# TemperatureReader.net
KiCad netlist of a schematic drawn in EAGLE
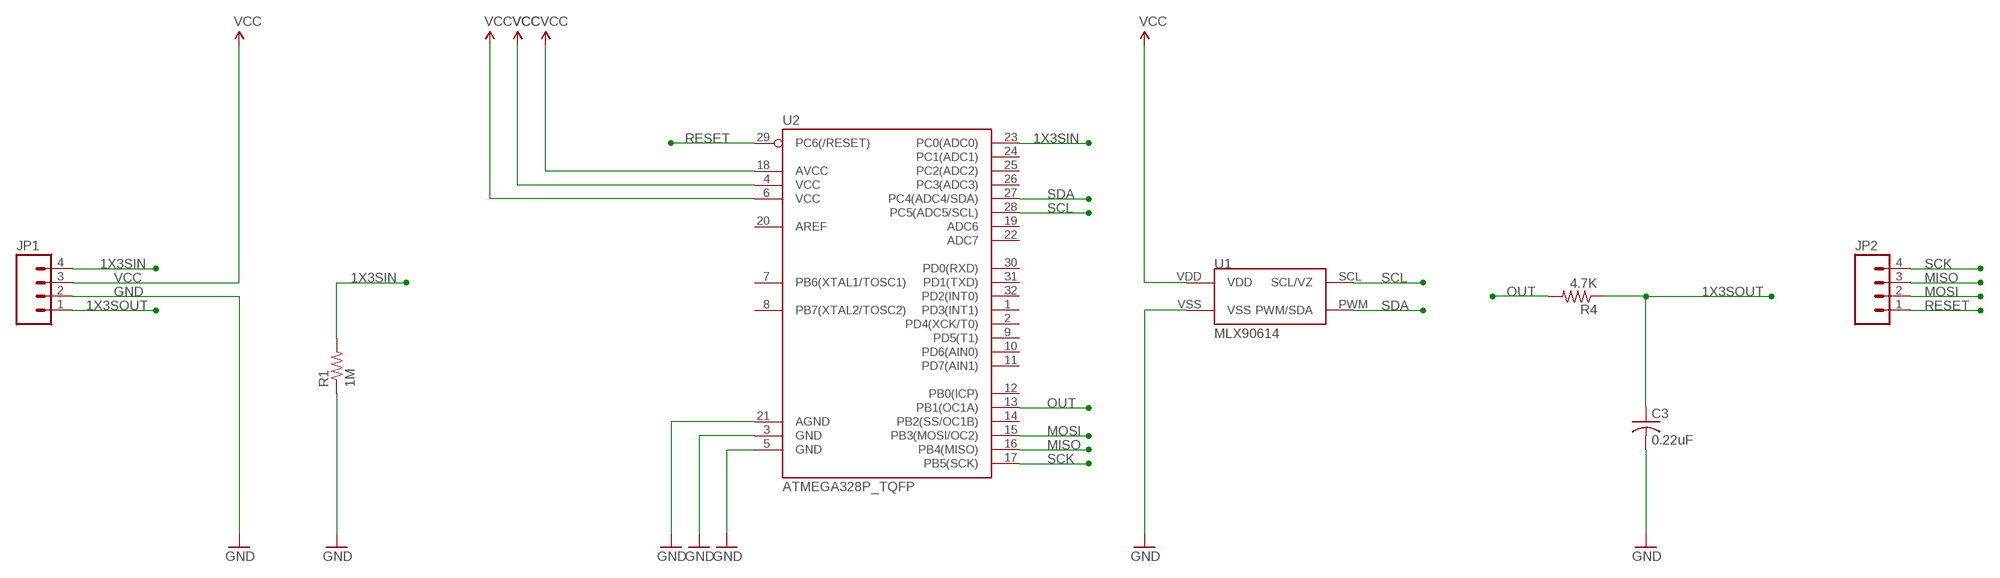
[diagram p0: schematic, sheet 1]

(export (version "E")
  (design (tool "Eeschema 10.0.6"))
  (components
    (comp (ref "C3")
      (value "0.22uF")
      (footprint "eagle-import:C0603")
      (libsource (lib "eagle-import") (part "C-USC0603"))
    )
    (comp (ref "JP1")
      (value "M04PTH")
      (footprint "eagle-import:1X04")
      (libsource (lib "eagle-import") (part "M04PTH"))
    )
    (comp (ref "JP2")
      (value "M04PTH")
      (footprint "eagle-import:1X04")
      (libsource (lib "eagle-import") (part "M04PTH"))
    )
    (comp (ref "R1")
      (value "1M")
      (footprint "eagle-import:R0603")
      (libsource (lib "eagle-import") (part "R-US_R0603"))
    )
    (comp (ref "R4")
      (value "4.7K")
      (footprint "eagle-import:R0603")
      (libsource (lib "eagle-import") (part "R-US_R0603"))
    )
    (comp (ref "U1")
      (value "MLX90614")
      (footprint "eagle-import:TO-39")
      (libsource (lib "eagle-import") (part "MLX90614"))
    )
    (comp (ref "U2")
      (value "ATMEGA328P_TQFP")
      (footprint "eagle-import:TQFP32-08")
      (libsource (lib "eagle-import") (part "ATMEGA328P_TQFP"))
    )
  )
  (nets
    (net (code "1") (name "/1X3SIN") (class "Default")
      (node (ref "JP1") (pin "4") (pinfunction "4_4") (pintype "passive"))
      (node (ref "R1") (pin "2") (pinfunction "2_2") (pintype "passive"))
      (node (ref "U2") (pin "23") (pinfunction "PC0(ADC0)_23") (pintype "bidirectional"))
    )
    (net (code "2") (name "/1X3SOUT") (class "Default")
      (node (ref "C3") (pin "1") (pinfunction "1_1") (pintype "passive"))
      (node (ref "JP1") (pin "1") (pinfunction "1_1") (pintype "passive"))
      (node (ref "R4") (pin "1") (pinfunction "1_1") (pintype "passive"))
    )
    (net (code "3") (name "/MISO") (class "Default")
      (node (ref "JP2") (pin "3") (pinfunction "3_3") (pintype "passive"))
      (node (ref "U2") (pin "16") (pinfunction "PB4(MISO)_16") (pintype "bidirectional"))
    )
    (net (code "4") (name "/MOSI") (class "Default")
      (node (ref "JP2") (pin "2") (pinfunction "2_2") (pintype "passive"))
      (node (ref "U2") (pin "15") (pinfunction "PB3(MOSI/OC2)_15") (pintype "bidirectional"))
    )
    (net (code "5") (name "/OUT") (class "Default")
      (node (ref "R4") (pin "2") (pinfunction "2_2") (pintype "passive"))
      (node (ref "U2") (pin "13") (pinfunction "PB1(OC1A)_13") (pintype "bidirectional"))
    )
    (net (code "6") (name "/RESET") (class "Default")
      (node (ref "JP2") (pin "1") (pinfunction "1_1") (pintype "passive"))
      (node (ref "U2") (pin "29") (pinfunction "PC6(/RESET)_29") (pintype "bidirectional"))
    )
    (net (code "7") (name "/SCK") (class "Default")
      (node (ref "JP2") (pin "4") (pinfunction "4_4") (pintype "passive"))
      (node (ref "U2") (pin "17") (pinfunction "PB5(SCK)_17") (pintype "bidirectional"))
    )
    (net (code "8") (name "/SCL") (class "Default")
      (node (ref "U1") (pin "SCL") (pinfunction "SCL/VZ_SCL") (pintype "bidirectional"))
      (node (ref "U2") (pin "28") (pinfunction "PC5(ADC5/SCL)_28") (pintype "bidirectional"))
    )
    (net (code "9") (name "/SDA") (class "Default")
      (node (ref "U1") (pin "PWM") (pinfunction "PWM/SDA_PWM") (pintype "bidirectional"))
      (node (ref "U2") (pin "27") (pinfunction "PC4(ADC4/SDA)_27") (pintype "bidirectional"))
    )
    (net (code "10") (name "GND") (class "Default")
      (node (ref "C3") (pin "2") (pinfunction "2_2") (pintype "passive"))
      (node (ref "JP1") (pin "2") (pinfunction "2_2") (pintype "passive"))
      (node (ref "R1") (pin "1") (pinfunction "1_1") (pintype "passive"))
      (node (ref "U1") (pin "VSS") (pinfunction "VSS_VSS") (pintype "bidirectional"))
      (node (ref "U2") (pin "21") (pinfunction "AGND_21") (pintype "bidirectional"))
      (node (ref "U2") (pin "3") (pinfunction "GND_3") (pintype "bidirectional"))
      (node (ref "U2") (pin "5") (pinfunction "GND_5") (pintype "bidirectional"))
    )
    (net (code "11") (name "VCC") (class "Default")
      (node (ref "JP1") (pin "3") (pinfunction "3_3") (pintype "passive"))
      (node (ref "U1") (pin "VDD") (pinfunction "VDD_VDD") (pintype "bidirectional"))
      (node (ref "U2") (pin "18") (pinfunction "AVCC_18") (pintype "bidirectional"))
      (node (ref "U2") (pin "4") (pinfunction "VCC_4") (pintype "bidirectional"))
      (node (ref "U2") (pin "6") (pinfunction "VCC_6") (pintype "bidirectional"))
    )
    (net (code "12") (name "unconnected-(U2-ADC6-Pad19)") (class "Default")
      (node (ref "U2") (pin "19") (pinfunction "ADC6_19") (pintype "bidirectional"))
    )
    (net (code "13") (name "unconnected-(U2-ADC7-Pad22)") (class "Default")
      (node (ref "U2") (pin "22") (pinfunction "ADC7_22") (pintype "bidirectional"))
    )
    (net (code "14") (name "unconnected-(U2-AREF-Pad20)") (class "Default")
      (node (ref "U2") (pin "20") (pinfunction "AREF_20") (pintype "bidirectional"))
    )
    (net (code "15") (name "unconnected-(U2-PB0(ICP)-Pad12)") (class "Default")
      (node (ref "U2") (pin "12") (pinfunction "PB0(ICP)_12") (pintype "bidirectional"))
    )
    (net (code "16") (name "unconnected-(U2-PB2(SS{slash}OC1B)-Pad14)") (class "Default")
      (node (ref "U2") (pin "14") (pinfunction "PB2(SS/OC1B)_14") (pintype "bidirectional"))
    )
    (net (code "17") (name "unconnected-(U2-PB6(XTAL1{slash}TOSC1)-Pad7)") (class "Default")
      (node (ref "U2") (pin "7") (pinfunction "PB6(XTAL1/TOSC1)_7") (pintype "bidirectional"))
    )
    (net (code "18") (name "unconnected-(U2-PB7(XTAL2{slash}TOSC2)-Pad8)") (class "Default")
      (node (ref "U2") (pin "8") (pinfunction "PB7(XTAL2/TOSC2)_8") (pintype "bidirectional"))
    )
    (net (code "19") (name "unconnected-(U2-PC1(ADC1)-Pad24)") (class "Default")
      (node (ref "U2") (pin "24") (pinfunction "PC1(ADC1)_24") (pintype "bidirectional"))
    )
    (net (code "20") (name "unconnected-(U2-PC2(ADC2)-Pad25)") (class "Default")
      (node (ref "U2") (pin "25") (pinfunction "PC2(ADC2)_25") (pintype "bidirectional"))
    )
    (net (code "21") (name "unconnected-(U2-PC3(ADC3)-Pad26)") (class "Default")
      (node (ref "U2") (pin "26") (pinfunction "PC3(ADC3)_26") (pintype "bidirectional"))
    )
    (net (code "22") (name "unconnected-(U2-PD0(RXD)-Pad30)") (class "Default")
      (node (ref "U2") (pin "30") (pinfunction "PD0(RXD)_30") (pintype "bidirectional"))
    )
    (net (code "23") (name "unconnected-(U2-PD1(TXD)-Pad31)") (class "Default")
      (node (ref "U2") (pin "31") (pinfunction "PD1(TXD)_31") (pintype "bidirectional"))
    )
    (net (code "24") (name "unconnected-(U2-PD2(INT0)-Pad32)") (class "Default")
      (node (ref "U2") (pin "32") (pinfunction "PD2(INT0)_32") (pintype "bidirectional"))
    )
    (net (code "25") (name "unconnected-(U2-PD3(INT1)-Pad1)") (class "Default")
      (node (ref "U2") (pin "1") (pinfunction "PD3(INT1)_1") (pintype "bidirectional"))
    )
    (net (code "26") (name "unconnected-(U2-PD4(XCK{slash}T0)-Pad2)") (class "Default")
      (node (ref "U2") (pin "2") (pinfunction "PD4(XCK/T0)_2") (pintype "bidirectional"))
    )
    (net (code "27") (name "unconnected-(U2-PD5(T1)-Pad9)") (class "Default")
      (node (ref "U2") (pin "9") (pinfunction "PD5(T1)_9") (pintype "bidirectional"))
    )
    (net (code "28") (name "unconnected-(U2-PD6(AIN0)-Pad10)") (class "Default")
      (node (ref "U2") (pin "10") (pinfunction "PD6(AIN0)_10") (pintype "bidirectional"))
    )
    (net (code "29") (name "unconnected-(U2-PD7(AIN1)-Pad11)") (class "Default")
      (node (ref "U2") (pin "11") (pinfunction "PD7(AIN1)_11") (pintype "bidirectional"))
    )
  )
)
